# POWER.net
KiCad netlist of a schematic drawn in Altium Designer
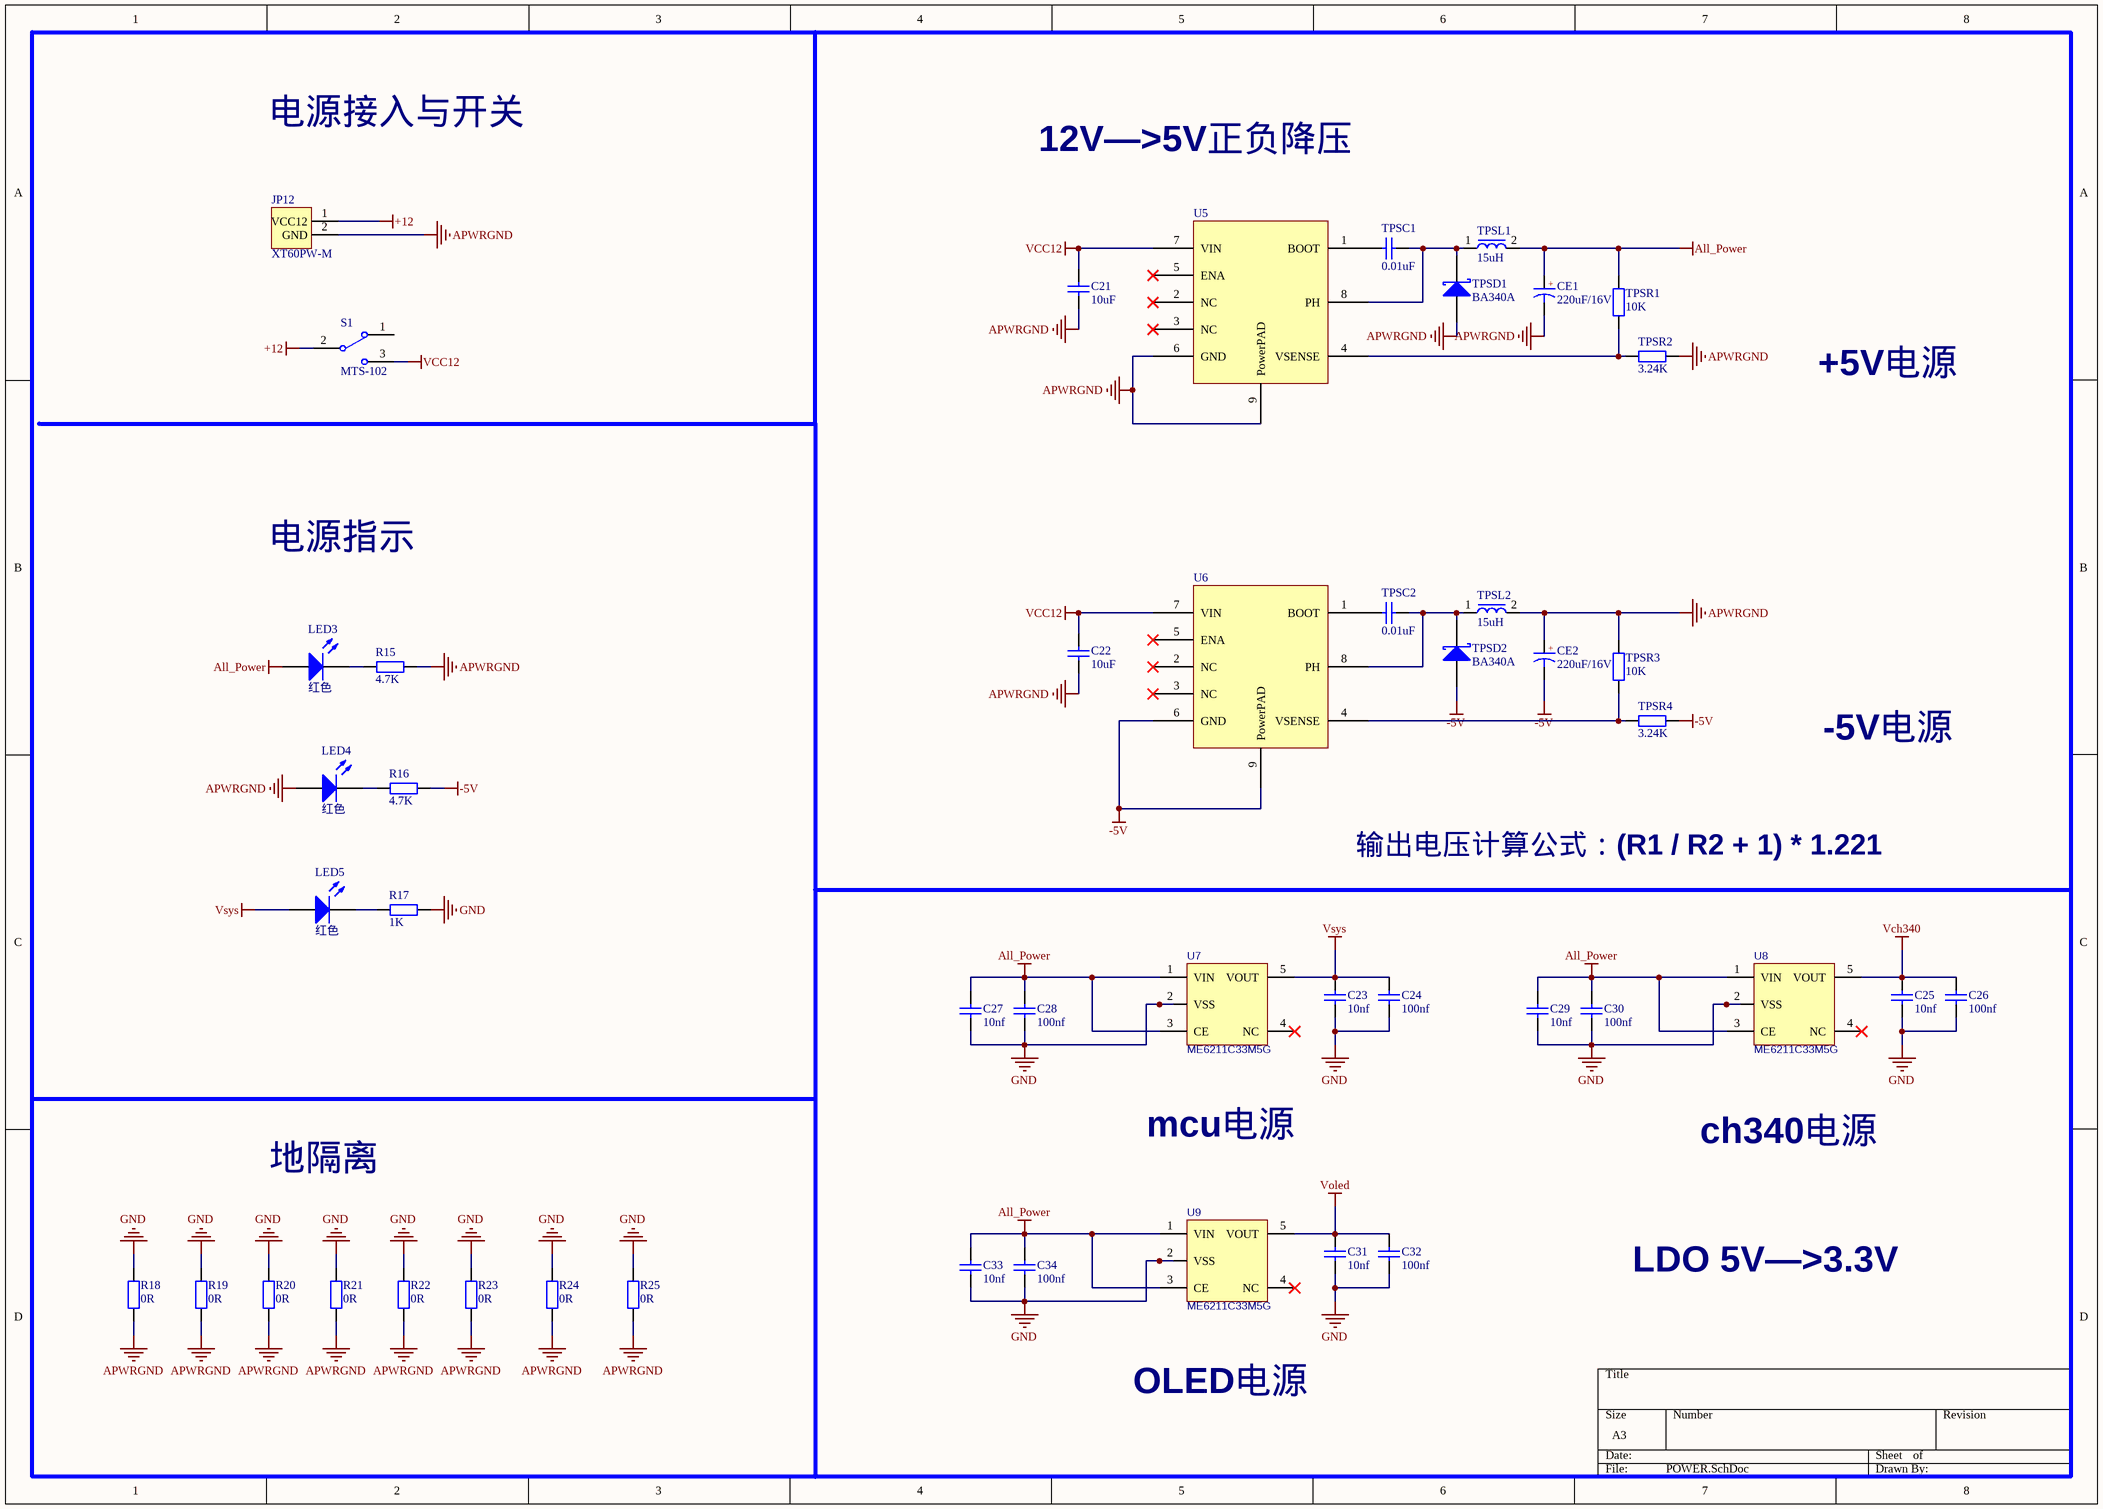
[diagram p0: POWER.SchDoc]

(export (version "E")
  (design (tool "Eeschema 10.0.6"))
  (components
    (comp (ref "C21")
      (value "10uF")
      (footprint "C0603_M")
      (description "贴片电容/MLCC电容")
      (libsource (lib "0.1 - 电阻-电容-电感-保险丝-晶振-晶体-磁珠-电位器-法拉电容-馈通电容") (part "C"))
    )
    (comp (ref "C22")
      (value "10uF")
      (footprint "C0603_M")
      (description "贴片电容/MLCC电容")
      (libsource (lib "0.1 - 电阻-电容-电感-保险丝-晶振-晶体-磁珠-电位器-法拉电容-馈通电容") (part "C"))
    )
    (comp (ref "C23")
      (value "10nf")
      (footprint "C0603_M")
      (description "贴片电容")
      (libsource (lib "cdud开发板") (part "C_3"))
    )
    (comp (ref "C24")
      (value "100nf")
      (footprint "C0603_M")
      (description "贴片电容")
      (libsource (lib "cdud开发板") (part "C_3"))
    )
    (comp (ref "C25")
      (value "10nf")
      (footprint "C0603_M")
      (description "贴片电容")
      (libsource (lib "cdud开发板") (part "C_3"))
    )
    (comp (ref "C26")
      (value "100nf")
      (footprint "C0603_M")
      (description "贴片电容")
      (libsource (lib "cdud开发板") (part "C_3"))
    )
    (comp (ref "C27")
      (value "10nf")
      (footprint "C0603_M")
      (description "贴片电容")
      (libsource (lib "cdud开发板") (part "C_3"))
    )
    (comp (ref "C28")
      (value "100nf")
      (footprint "C0603_M")
      (description "贴片电容")
      (libsource (lib "cdud开发板") (part "C_3"))
    )
    (comp (ref "C29")
      (value "10nf")
      (footprint "C0603_M")
      (description "贴片电容")
      (libsource (lib "cdud开发板") (part "C_3"))
    )
    (comp (ref "C30")
      (value "100nf")
      (footprint "C0603_M")
      (description "贴片电容")
      (libsource (lib "cdud开发板") (part "C_3"))
    )
    (comp (ref "C31")
      (value "10nf")
      (footprint "C0603_M")
      (description "贴片电容")
      (libsource (lib "cdud开发板") (part "C_3"))
    )
    (comp (ref "C32")
      (value "100nf")
      (footprint "C0603_M")
      (description "贴片电容")
      (libsource (lib "cdud开发板") (part "C_3"))
    )
    (comp (ref "C33")
      (value "10nf")
      (footprint "C0603_M")
      (description "贴片电容")
      (libsource (lib "cdud开发板") (part "C_3"))
    )
    (comp (ref "C34")
      (value "100nf")
      (footprint "C0603_M")
      (description "贴片电容")
      (libsource (lib "cdud开发板") (part "C_3"))
    )
    (comp (ref "CE1")
      (value "220uF/16V")
      (footprint "CE D(6.3*5.4)")
      (description "直插电解电容")
      (libsource (lib "0.1 - 电阻-电容-电感-晶振-晶体-磁珠-电位器") (part "CE"))
    )
    (comp (ref "CE2")
      (value "220uF/16V")
      (footprint "CE D(6.3*5.4)")
      (description "直插电解电容")
      (libsource (lib "0.1 - 电阻-电容-电感-晶振-晶体-磁珠-电位器") (part "CE"))
    )
    (comp (ref "JP12")
      (value "XT60PW-M")
      (footprint "TX60PW-M20")
      (description "XT60PW-M弯插")
      (libsource (lib "XT60PW") (part "XT60PW"))
    )
    (comp (ref "LED3")
      (value "红色")
      (footprint "LED0603_R")
      (description "贴片LED")
      (libsource (lib "0.3 - LED发光二极管-IR二极管_接收管-光耦") (part "LED"))
    )
    (comp (ref "LED4")
      (value "红色")
      (footprint "LED0603_R")
      (description "贴片LED")
      (libsource (lib "0.3 - LED发光二极管-IR二极管_接收管-光耦") (part "LED"))
    )
    (comp (ref "LED5")
      (value "红色")
      (footprint "LED0603_R")
      (description "贴片LED")
      (libsource (lib "0.3 - LED发光二极管-IR二极管_接收管-光耦") (part "LED"))
    )
    (comp (ref "R15")
      (value "4.7K")
      (footprint "R0603_M")
      (description "贴片电阻")
      (libsource (lib "cdud开发板") (part "R"))
    )
    (comp (ref "R16")
      (value "4.7K")
      (footprint "R0603_M")
      (description "贴片电阻")
      (libsource (lib "cdud开发板") (part "R"))
    )
    (comp (ref "R17")
      (value "1K")
      (footprint "R0603_M")
      (description "贴片电阻")
      (libsource (lib "0.1 - 电阻-电容-电感-晶振-晶体-磁珠-电位器") (part "R"))
    )
    (comp (ref "R18")
      (value "0R")
      (footprint "R0603_M")
      (description "贴片电阻")
      (libsource (lib "0.1 - 电阻-电容-电感-保险丝-晶振-晶体-磁珠-电位器-法拉电容-馈通电容") (part "R"))
    )
    (comp (ref "R19")
      (value "0R")
      (footprint "R0603_M")
      (description "贴片电阻")
      (libsource (lib "0.1 - 电阻-电容-电感-保险丝-晶振-晶体-磁珠-电位器-法拉电容-馈通电容") (part "R"))
    )
    (comp (ref "R20")
      (value "0R")
      (footprint "R0603_M")
      (description "贴片电阻")
      (libsource (lib "0.1 - 电阻-电容-电感-保险丝-晶振-晶体-磁珠-电位器-法拉电容-馈通电容") (part "R"))
    )
    (comp (ref "R21")
      (value "0R")
      (footprint "R0603_M")
      (description "贴片电阻")
      (libsource (lib "0.1 - 电阻-电容-电感-保险丝-晶振-晶体-磁珠-电位器-法拉电容-馈通电容") (part "R"))
    )
    (comp (ref "R22")
      (value "0R")
      (footprint "R0603_M")
      (description "贴片电阻")
      (libsource (lib "0.1 - 电阻-电容-电感-保险丝-晶振-晶体-磁珠-电位器-法拉电容-馈通电容") (part "R"))
    )
    (comp (ref "R23")
      (value "0R")
      (footprint "R0603_M")
      (description "贴片电阻")
      (libsource (lib "0.1 - 电阻-电容-电感-保险丝-晶振-晶体-磁珠-电位器-法拉电容-馈通电容") (part "R"))
    )
    (comp (ref "R24")
      (value "0R")
      (footprint "R0603_M")
      (description "贴片电阻")
      (libsource (lib "0.1 - 电阻-电容-电感-保险丝-晶振-晶体-磁珠-电位器-法拉电容-馈通电容") (part "R"))
    )
    (comp (ref "R25")
      (value "0R")
      (footprint "R0603_M")
      (description "贴片电阻")
      (libsource (lib "0.1 - 电阻-电容-电感-保险丝-晶振-晶体-磁珠-电位器-法拉电容-馈通电容") (part "R"))
    )
    (comp (ref "S1")
      (value "MTS-102")
      (footprint "MTS-10x")
      (description "MTS10x系列3脚扭子开关")
      (fields (field (name "版权归属") "源创客"))
      (libsource (lib "S109Controller") (part "MTS-10x"))
    )
    (comp (ref "TPSC1")
      (value "0.01uF")
      (footprint "C0603_M")
      (description "贴片电容")
      (libsource (lib "0.1 - 电阻-电容-电感-晶振-晶体-磁珠-电位器") (part "C"))
    )
    (comp (ref "TPSC2")
      (value "0.01uF")
      (footprint "C0603_M")
      (description "贴片电容")
      (libsource (lib "0.1 - 电阻-电容-电感-晶振-晶体-磁珠-电位器") (part "C"))
    )
    (comp (ref "TPSD1")
      (value "BA340A")
      (footprint "SMC")
      (description "肖特基二极管")
      (libsource (lib "0.2 - 二极管-TVS-ESD-整流桥") (part "SS210"))
    )
    (comp (ref "TPSD2")
      (value "BA340A")
      (footprint "SMC")
      (description "肖特基二极管")
      (libsource (lib "0.2 - 二极管-TVS-ESD-整流桥") (part "SS210"))
    )
    (comp (ref "TPSL1")
      (value "15uH")
      (footprint "CDRH74")
      (description "SMA")
      (libsource (lib "mylibrary") (part "L 0630"))
    )
    (comp (ref "TPSL2")
      (value "15uH")
      (footprint "CDRH74")
      (description "SMA")
      (libsource (lib "mylibrary") (part "L 0630"))
    )
    (comp (ref "TPSR1")
      (value "10K")
      (footprint "R0603_M")
      (description "贴片电阻")
      (libsource (lib "0.1 - 电阻-电容-电感-晶振-晶体-磁珠-电位器") (part "R"))
    )
    (comp (ref "TPSR2")
      (value "3.24K")
      (footprint "R0603_M")
      (description "贴片电阻")
      (libsource (lib "0.1 - 电阻-电容-电感-晶振-晶体-磁珠-电位器") (part "R"))
    )
    (comp (ref "TPSR3")
      (value "10K")
      (footprint "R0603_M")
      (description "贴片电阻")
      (libsource (lib "0.1 - 电阻-电容-电感-晶振-晶体-磁珠-电位器") (part "R"))
    )
    (comp (ref "TPSR4")
      (value "3.24K")
      (footprint "R0603_M")
      (description "贴片电阻")
      (libsource (lib "0.1 - 电阻-电容-电感-晶振-晶体-磁珠-电位器") (part "R"))
    )
    (comp (ref "U5")
      (value "TPS5430DDAR")
      (footprint "SOP8_M")
      (description "输出额定电流3A 纹波30mV")
      (libsource (lib "mylibrary") (part "TPS5430DDAR"))
    )
    (comp (ref "U6")
      (value "TPS5430DDAR")
      (footprint "SOP8_M")
      (description "输出额定电流3A 纹波30mV")
      (libsource (lib "mylibrary") (part "TPS5430DDAR"))
    )
    (comp (ref "U7")
      (value "ME6211C33M5G")
      (footprint "SOT23-5N")
      (description "LDO 3.3V/0.5A")
      (libsource (lib "0.7 - 电源类芯片") (part "ME6211C33"))
    )
    (comp (ref "U8")
      (value "ME6211C33M5G")
      (footprint "SOT23-5N")
      (description "LDO 3.3V/0.5A")
      (libsource (lib "0.7 - 电源类芯片") (part "ME6211C33"))
    )
    (comp (ref "U9")
      (value "ME6211C33M5G")
      (footprint "SOT23-5N")
      (description "LDO 3.3V/0.5A")
      (libsource (lib "0.7 - 电源类芯片") (part "ME6211C33"))
    )
  )
  (nets
    (net (code "1") (name "+12") (class "Default")
      (node (ref "JP12") (pin "1") (pinfunction "VCC12_1") (pintype "passive"))
      (node (ref "S1") (pin "2") (pinfunction "2_2") (pintype "passive"))
    )
    (net (code "2") (name "-5V") (class "Default")
      (node (ref "CE2") (pin "2") (pinfunction "2_2") (pintype "passive"))
      (node (ref "R16") (pin "1") (pinfunction "1_1") (pintype "passive"))
      (node (ref "TPSD2") (pin "1") (pinfunction "A_1") (pintype "passive"))
      (node (ref "TPSR4") (pin "1") (pinfunction "1_1") (pintype "passive"))
      (node (ref "U6") (pin "6") (pinfunction "GND_6") (pintype "passive"))
      (node (ref "U6") (pin "9") (pinfunction "PowerPAD_9") (pintype "passive"))
    )
    (net (code "3") (name "APWRGND") (class "Default")
      (node (ref "C21") (pin "1") (pinfunction "1_1") (pintype "passive"))
      (node (ref "C22") (pin "1") (pinfunction "1_1") (pintype "passive"))
      (node (ref "CE1") (pin "2") (pinfunction "2_2") (pintype "passive"))
      (node (ref "CE2") (pin "1") (pinfunction "1_1") (pintype "passive"))
      (node (ref "JP12") (pin "2") (pinfunction "GND_2") (pintype "passive"))
      (node (ref "LED4") (pin "1") (pinfunction "A_1") (pintype "passive"))
      (node (ref "R15") (pin "1") (pinfunction "1_1") (pintype "passive"))
      (node (ref "R18") (pin "2") (pinfunction "2_2") (pintype "passive"))
      (node (ref "R19") (pin "2") (pinfunction "2_2") (pintype "passive"))
      (node (ref "R20") (pin "2") (pinfunction "2_2") (pintype "passive"))
      (node (ref "R21") (pin "2") (pinfunction "2_2") (pintype "passive"))
      (node (ref "R22") (pin "2") (pinfunction "2_2") (pintype "passive"))
      (node (ref "R23") (pin "2") (pinfunction "2_2") (pintype "passive"))
      (node (ref "R24") (pin "2") (pinfunction "2_2") (pintype "passive"))
      (node (ref "R25") (pin "2") (pinfunction "2_2") (pintype "passive"))
      (node (ref "TPSD1") (pin "1") (pinfunction "A_1") (pintype "passive"))
      (node (ref "TPSL2") (pin "2") (pinfunction "2_2") (pintype "passive"))
      (node (ref "TPSR2") (pin "1") (pinfunction "1_1") (pintype "passive"))
      (node (ref "TPSR3") (pin "2") (pinfunction "2_2") (pintype "passive"))
      (node (ref "U5") (pin "6") (pinfunction "GND_6") (pintype "passive"))
      (node (ref "U5") (pin "9") (pinfunction "PowerPAD_9") (pintype "passive"))
    )
    (net (code "4") (name "All_Power") (class "Default")
      (node (ref "C27") (pin "2") (pinfunction "2_2") (pintype "passive"))
      (node (ref "C28") (pin "2") (pinfunction "2_2") (pintype "passive"))
      (node (ref "C29") (pin "2") (pinfunction "2_2") (pintype "passive"))
      (node (ref "C30") (pin "2") (pinfunction "2_2") (pintype "passive"))
      (node (ref "C33") (pin "2") (pinfunction "2_2") (pintype "passive"))
      (node (ref "C34") (pin "2") (pinfunction "2_2") (pintype "passive"))
      (node (ref "CE1") (pin "1") (pinfunction "1_1") (pintype "passive"))
      (node (ref "LED3") (pin "1") (pinfunction "A_1") (pintype "passive"))
      (node (ref "TPSL1") (pin "2") (pinfunction "2_2") (pintype "passive"))
      (node (ref "TPSR1") (pin "2") (pinfunction "2_2") (pintype "passive"))
      (node (ref "U7") (pin "1") (pinfunction "VIN_1") (pintype "passive"))
      (node (ref "U7") (pin "3") (pinfunction "CE_3") (pintype "passive"))
      (node (ref "U8") (pin "1") (pinfunction "VIN_1") (pintype "passive"))
      (node (ref "U8") (pin "3") (pinfunction "CE_3") (pintype "passive"))
      (node (ref "U9") (pin "1") (pinfunction "VIN_1") (pintype "passive"))
      (node (ref "U9") (pin "3") (pinfunction "CE_3") (pintype "passive"))
    )
    (net (code "5") (name "GND") (class "Default")
      (node (ref "C23") (pin "1") (pinfunction "1_1") (pintype "passive"))
      (node (ref "C24") (pin "1") (pinfunction "1_1") (pintype "passive"))
      (node (ref "C25") (pin "1") (pinfunction "1_1") (pintype "passive"))
      (node (ref "C26") (pin "1") (pinfunction "1_1") (pintype "passive"))
      (node (ref "C27") (pin "1") (pinfunction "1_1") (pintype "passive"))
      (node (ref "C28") (pin "1") (pinfunction "1_1") (pintype "passive"))
      (node (ref "C29") (pin "1") (pinfunction "1_1") (pintype "passive"))
      (node (ref "C30") (pin "1") (pinfunction "1_1") (pintype "passive"))
      (node (ref "C31") (pin "1") (pinfunction "1_1") (pintype "passive"))
      (node (ref "C32") (pin "1") (pinfunction "1_1") (pintype "passive"))
      (node (ref "C33") (pin "1") (pinfunction "1_1") (pintype "passive"))
      (node (ref "C34") (pin "1") (pinfunction "1_1") (pintype "passive"))
      (node (ref "R17") (pin "2") (pinfunction "2_2") (pintype "passive"))
      (node (ref "R18") (pin "1") (pinfunction "1_1") (pintype "passive"))
      (node (ref "R19") (pin "1") (pinfunction "1_1") (pintype "passive"))
      (node (ref "R20") (pin "1") (pinfunction "1_1") (pintype "passive"))
      (node (ref "R21") (pin "1") (pinfunction "1_1") (pintype "passive"))
      (node (ref "R22") (pin "1") (pinfunction "1_1") (pintype "passive"))
      (node (ref "R23") (pin "1") (pinfunction "1_1") (pintype "passive"))
      (node (ref "R24") (pin "1") (pinfunction "1_1") (pintype "passive"))
      (node (ref "R25") (pin "1") (pinfunction "1_1") (pintype "passive"))
      (node (ref "U7") (pin "2") (pinfunction "VSS_2") (pintype "passive"))
      (node (ref "U8") (pin "2") (pinfunction "VSS_2") (pintype "passive"))
      (node (ref "U9") (pin "2") (pinfunction "VSS_2") (pintype "passive"))
    )
    (net (code "6") (name "Net-(LED3-K)") (class "Default")
      (node (ref "LED3") (pin "2") (pinfunction "K_2") (pintype "passive"))
      (node (ref "R15") (pin "2") (pinfunction "2_2") (pintype "passive"))
    )
    (net (code "7") (name "Net-(LED4-K)") (class "Default")
      (node (ref "LED4") (pin "2") (pinfunction "K_2") (pintype "passive"))
      (node (ref "R16") (pin "2") (pinfunction "2_2") (pintype "passive"))
    )
    (net (code "8") (name "Net-(LED5-K)") (class "Default")
      (node (ref "LED5") (pin "2") (pinfunction "K_2") (pintype "passive"))
      (node (ref "R17") (pin "1") (pinfunction "1_1") (pintype "passive"))
    )
    (net (code "9") (name "Net-(TPSD1-K)") (class "Default")
      (node (ref "TPSC1") (pin "1") (pinfunction "1_1") (pintype "passive"))
      (node (ref "TPSD1") (pin "2") (pinfunction "K_2") (pintype "passive"))
      (node (ref "TPSL1") (pin "1") (pinfunction "1_1") (pintype "passive"))
      (node (ref "U5") (pin "8") (pinfunction "PH_8") (pintype "passive"))
    )
    (net (code "10") (name "Net-(TPSD2-K)") (class "Default")
      (node (ref "TPSC2") (pin "1") (pinfunction "1_1") (pintype "passive"))
      (node (ref "TPSD2") (pin "2") (pinfunction "K_2") (pintype "passive"))
      (node (ref "TPSL2") (pin "1") (pinfunction "1_1") (pintype "passive"))
      (node (ref "U6") (pin "8") (pinfunction "PH_8") (pintype "passive"))
    )
    (net (code "11") (name "Net-(U5-BOOT)") (class "Default")
      (node (ref "TPSC1") (pin "2") (pinfunction "2_2") (pintype "passive"))
      (node (ref "U5") (pin "1") (pinfunction "BOOT_1") (pintype "passive"))
    )
    (net (code "12") (name "Net-(U5-VSENSE)") (class "Default")
      (node (ref "TPSR1") (pin "1") (pinfunction "1_1") (pintype "passive"))
      (node (ref "TPSR2") (pin "2") (pinfunction "2_2") (pintype "passive"))
      (node (ref "U5") (pin "4") (pinfunction "VSENSE_4") (pintype "passive"))
    )
    (net (code "13") (name "Net-(U6-BOOT)") (class "Default")
      (node (ref "TPSC2") (pin "2") (pinfunction "2_2") (pintype "passive"))
      (node (ref "U6") (pin "1") (pinfunction "BOOT_1") (pintype "passive"))
    )
    (net (code "14") (name "Net-(U6-VSENSE)") (class "Default")
      (node (ref "TPSR3") (pin "1") (pinfunction "1_1") (pintype "passive"))
      (node (ref "TPSR4") (pin "2") (pinfunction "2_2") (pintype "passive"))
      (node (ref "U6") (pin "4") (pinfunction "VSENSE_4") (pintype "passive"))
    )
    (net (code "15") (name "VCC12") (class "Default")
      (node (ref "C21") (pin "2") (pinfunction "2_2") (pintype "passive"))
      (node (ref "C22") (pin "2") (pinfunction "2_2") (pintype "passive"))
      (node (ref "S1") (pin "3") (pinfunction "3_3") (pintype "passive"))
      (node (ref "U5") (pin "7") (pinfunction "VIN_7") (pintype "passive"))
      (node (ref "U6") (pin "7") (pinfunction "VIN_7") (pintype "passive"))
    )
    (net (code "16") (name "Vch340") (class "Default")
      (node (ref "C25") (pin "2") (pinfunction "2_2") (pintype "passive"))
      (node (ref "C26") (pin "2") (pinfunction "2_2") (pintype "passive"))
      (node (ref "U8") (pin "5") (pinfunction "VOUT_5") (pintype "passive"))
    )
    (net (code "17") (name "Voled") (class "Default")
      (node (ref "C31") (pin "2") (pinfunction "2_2") (pintype "passive"))
      (node (ref "C32") (pin "2") (pinfunction "2_2") (pintype "passive"))
      (node (ref "U9") (pin "5") (pinfunction "VOUT_5") (pintype "passive"))
    )
    (net (code "18") (name "Vsys") (class "Default")
      (node (ref "C23") (pin "2") (pinfunction "2_2") (pintype "passive"))
      (node (ref "C24") (pin "2") (pinfunction "2_2") (pintype "passive"))
      (node (ref "LED5") (pin "1") (pinfunction "A_1") (pintype "passive"))
      (node (ref "U7") (pin "5") (pinfunction "VOUT_5") (pintype "passive"))
    )
    (net (code "19") (name "unconnected-(S1-Pad1)") (class "Default")
      (node (ref "S1") (pin "1") (pinfunction "1_1") (pintype "passive"))
    )
    (net (code "20") (name "unconnected-(U5-ENA-Pad5)") (class "Default")
      (node (ref "U5") (pin "5") (pinfunction "ENA_5") (pintype "passive+no_connect"))
    )
    (net (code "21") (name "unconnected-(U5-NC-Pad2)") (class "Default")
      (node (ref "U5") (pin "2") (pinfunction "NC_2") (pintype "passive+no_connect"))
    )
    (net (code "22") (name "unconnected-(U5-NC-Pad3)") (class "Default")
      (node (ref "U5") (pin "3") (pinfunction "NC_3") (pintype "passive+no_connect"))
    )
    (net (code "23") (name "unconnected-(U6-ENA-Pad5)") (class "Default")
      (node (ref "U6") (pin "5") (pinfunction "ENA_5") (pintype "passive+no_connect"))
    )
    (net (code "24") (name "unconnected-(U6-NC-Pad2)") (class "Default")
      (node (ref "U6") (pin "2") (pinfunction "NC_2") (pintype "passive+no_connect"))
    )
    (net (code "25") (name "unconnected-(U6-NC-Pad3)") (class "Default")
      (node (ref "U6") (pin "3") (pinfunction "NC_3") (pintype "passive+no_connect"))
    )
    (net (code "26") (name "unconnected-(U7-NC-Pad4)") (class "Default")
      (node (ref "U7") (pin "4") (pinfunction "NC_4") (pintype "passive+no_connect"))
    )
    (net (code "27") (name "unconnected-(U8-NC-Pad4)") (class "Default")
      (node (ref "U8") (pin "4") (pinfunction "NC_4") (pintype "passive+no_connect"))
    )
    (net (code "28") (name "unconnected-(U9-NC-Pad4)") (class "Default")
      (node (ref "U9") (pin "4") (pinfunction "NC_4") (pintype "passive+no_connect"))
    )
  )
)
